# Top.net
KiCad netlist of a schematic drawn in Altium Designer
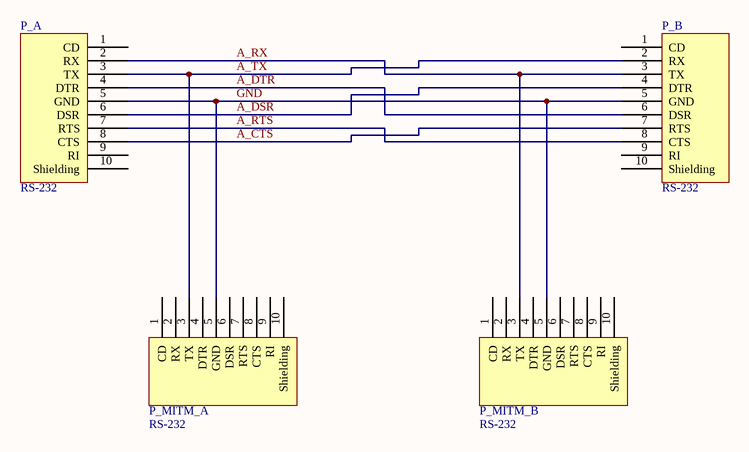
[diagram p0: Top.SchDoc]

(export (version "E")
  (design (tool "Eeschema 10.0.6"))
  (components
    (comp (ref "P_A")
      (value "RS-232")
      (footprint "RS232 SMD male")
      (libsource (lib "RS232-MITM") (part "RS-232"))
    )
    (comp (ref "P_B") (value "RS-232") (footprint "RS232 SMD male") (libsource (lib "") (part "RS-232_1")))
    (comp (ref "P_MITM_A")
      (value "RS-232")
      (footprint "RS232 SMD male")
      (libsource (lib "") (part "RS-232_2"))
    )
    (comp (ref "P_MITM_B")
      (value "RS-232")
      (footprint "RS232 SMD male")
      (libsource (lib "") (part "RS-232_2"))
    )
  )
  (nets
    (net (code "1") (name "/A_CTS") (class "Default")
      (node (ref "P_A") (pin "8") (pinfunction "CTS_8") (pintype "passive"))
      (node (ref "P_B") (pin "7") (pinfunction "RTS_7") (pintype "passive"))
    )
    (net (code "2") (name "/A_DSR") (class "Default")
      (node (ref "P_A") (pin "6") (pinfunction "DSR_6") (pintype "passive"))
      (node (ref "P_B") (pin "4") (pinfunction "DTR_4") (pintype "passive"))
    )
    (net (code "3") (name "/A_DTR") (class "Default")
      (node (ref "P_A") (pin "4") (pinfunction "DTR_4") (pintype "passive"))
      (node (ref "P_B") (pin "6") (pinfunction "DSR_6") (pintype "passive"))
    )
    (net (code "4") (name "/A_RTS") (class "Default")
      (node (ref "P_A") (pin "7") (pinfunction "RTS_7") (pintype "passive"))
      (node (ref "P_B") (pin "8") (pinfunction "CTS_8") (pintype "passive"))
    )
    (net (code "5") (name "/A_RX") (class "Default")
      (node (ref "P_A") (pin "2") (pinfunction "RX_2") (pintype "passive"))
      (node (ref "P_B") (pin "3") (pinfunction "TX_3") (pintype "passive"))
      (node (ref "P_MITM_B") (pin "3") (pinfunction "TX_3") (pintype "passive"))
    )
    (net (code "6") (name "/A_TX") (class "Default")
      (node (ref "P_A") (pin "3") (pinfunction "TX_3") (pintype "passive"))
      (node (ref "P_B") (pin "2") (pinfunction "RX_2") (pintype "passive"))
      (node (ref "P_MITM_A") (pin "3") (pinfunction "TX_3") (pintype "passive"))
    )
    (net (code "7") (name "/GND") (class "Default")
      (node (ref "P_A") (pin "5") (pinfunction "GND_5") (pintype "passive"))
      (node (ref "P_B") (pin "5") (pinfunction "GND_5") (pintype "passive"))
      (node (ref "P_MITM_A") (pin "5") (pinfunction "GND_5") (pintype "passive"))
      (node (ref "P_MITM_B") (pin "5") (pinfunction "GND_5") (pintype "passive"))
    )
    (net (code "8") (name "unconnected-(P_A-CD-Pad1)") (class "Default")
      (node (ref "P_A") (pin "1") (pinfunction "CD_1") (pintype "passive"))
    )
    (net (code "9") (name "unconnected-(P_A-RI-Pad9)") (class "Default")
      (node (ref "P_A") (pin "9") (pinfunction "RI_9") (pintype "passive"))
    )
    (net (code "10") (name "unconnected-(P_A-Shielding-Pad10)") (class "Default")
      (node (ref "P_A") (pin "10") (pinfunction "Shielding_10") (pintype "passive"))
    )
    (net (code "11") (name "unconnected-(P_B-CD-Pad1)") (class "Default")
      (node (ref "P_B") (pin "1") (pinfunction "CD_1") (pintype "passive"))
    )
    (net (code "12") (name "unconnected-(P_B-RI-Pad9)") (class "Default")
      (node (ref "P_B") (pin "9") (pinfunction "RI_9") (pintype "passive"))
    )
    (net (code "13") (name "unconnected-(P_B-Shielding-Pad10)") (class "Default")
      (node (ref "P_B") (pin "10") (pinfunction "Shielding_10") (pintype "passive"))
    )
    (net (code "14") (name "unconnected-(P_MITM_A-CD-Pad1)") (class "Default")
      (node (ref "P_MITM_A") (pin "1") (pinfunction "CD_1") (pintype "passive"))
    )
    (net (code "15") (name "unconnected-(P_MITM_A-CTS-Pad8)") (class "Default")
      (node (ref "P_MITM_A") (pin "8") (pinfunction "CTS_8") (pintype "passive"))
    )
    (net (code "16") (name "unconnected-(P_MITM_A-DSR-Pad6)") (class "Default")
      (node (ref "P_MITM_A") (pin "6") (pinfunction "DSR_6") (pintype "passive"))
    )
    (net (code "17") (name "unconnected-(P_MITM_A-DTR-Pad4)") (class "Default")
      (node (ref "P_MITM_A") (pin "4") (pinfunction "DTR_4") (pintype "passive"))
    )
    (net (code "18") (name "unconnected-(P_MITM_A-RI-Pad9)") (class "Default")
      (node (ref "P_MITM_A") (pin "9") (pinfunction "RI_9") (pintype "passive"))
    )
    (net (code "19") (name "unconnected-(P_MITM_A-RTS-Pad7)") (class "Default")
      (node (ref "P_MITM_A") (pin "7") (pinfunction "RTS_7") (pintype "passive"))
    )
    (net (code "20") (name "unconnected-(P_MITM_A-RX-Pad2)") (class "Default")
      (node (ref "P_MITM_A") (pin "2") (pinfunction "RX_2") (pintype "passive"))
    )
    (net (code "21") (name "unconnected-(P_MITM_A-Shielding-Pad10)") (class "Default")
      (node (ref "P_MITM_A") (pin "10") (pinfunction "Shielding_10") (pintype "passive"))
    )
    (net (code "22") (name "unconnected-(P_MITM_B-CD-Pad1)") (class "Default")
      (node (ref "P_MITM_B") (pin "1") (pinfunction "CD_1") (pintype "passive"))
    )
    (net (code "23") (name "unconnected-(P_MITM_B-CTS-Pad8)") (class "Default")
      (node (ref "P_MITM_B") (pin "8") (pinfunction "CTS_8") (pintype "passive"))
    )
    (net (code "24") (name "unconnected-(P_MITM_B-DSR-Pad6)") (class "Default")
      (node (ref "P_MITM_B") (pin "6") (pinfunction "DSR_6") (pintype "passive"))
    )
    (net (code "25") (name "unconnected-(P_MITM_B-DTR-Pad4)") (class "Default")
      (node (ref "P_MITM_B") (pin "4") (pinfunction "DTR_4") (pintype "passive"))
    )
    (net (code "26") (name "unconnected-(P_MITM_B-RI-Pad9)") (class "Default")
      (node (ref "P_MITM_B") (pin "9") (pinfunction "RI_9") (pintype "passive"))
    )
    (net (code "27") (name "unconnected-(P_MITM_B-RTS-Pad7)") (class "Default")
      (node (ref "P_MITM_B") (pin "7") (pinfunction "RTS_7") (pintype "passive"))
    )
    (net (code "28") (name "unconnected-(P_MITM_B-RX-Pad2)") (class "Default")
      (node (ref "P_MITM_B") (pin "2") (pinfunction "RX_2") (pintype "passive"))
    )
    (net (code "29") (name "unconnected-(P_MITM_B-Shielding-Pad10)") (class "Default")
      (node (ref "P_MITM_B") (pin "10") (pinfunction "Shielding_10") (pintype "passive"))
    )
  )
)
